# mcu1_secondary.net
KiCad netlist of a schematic drawn in Altium Designer
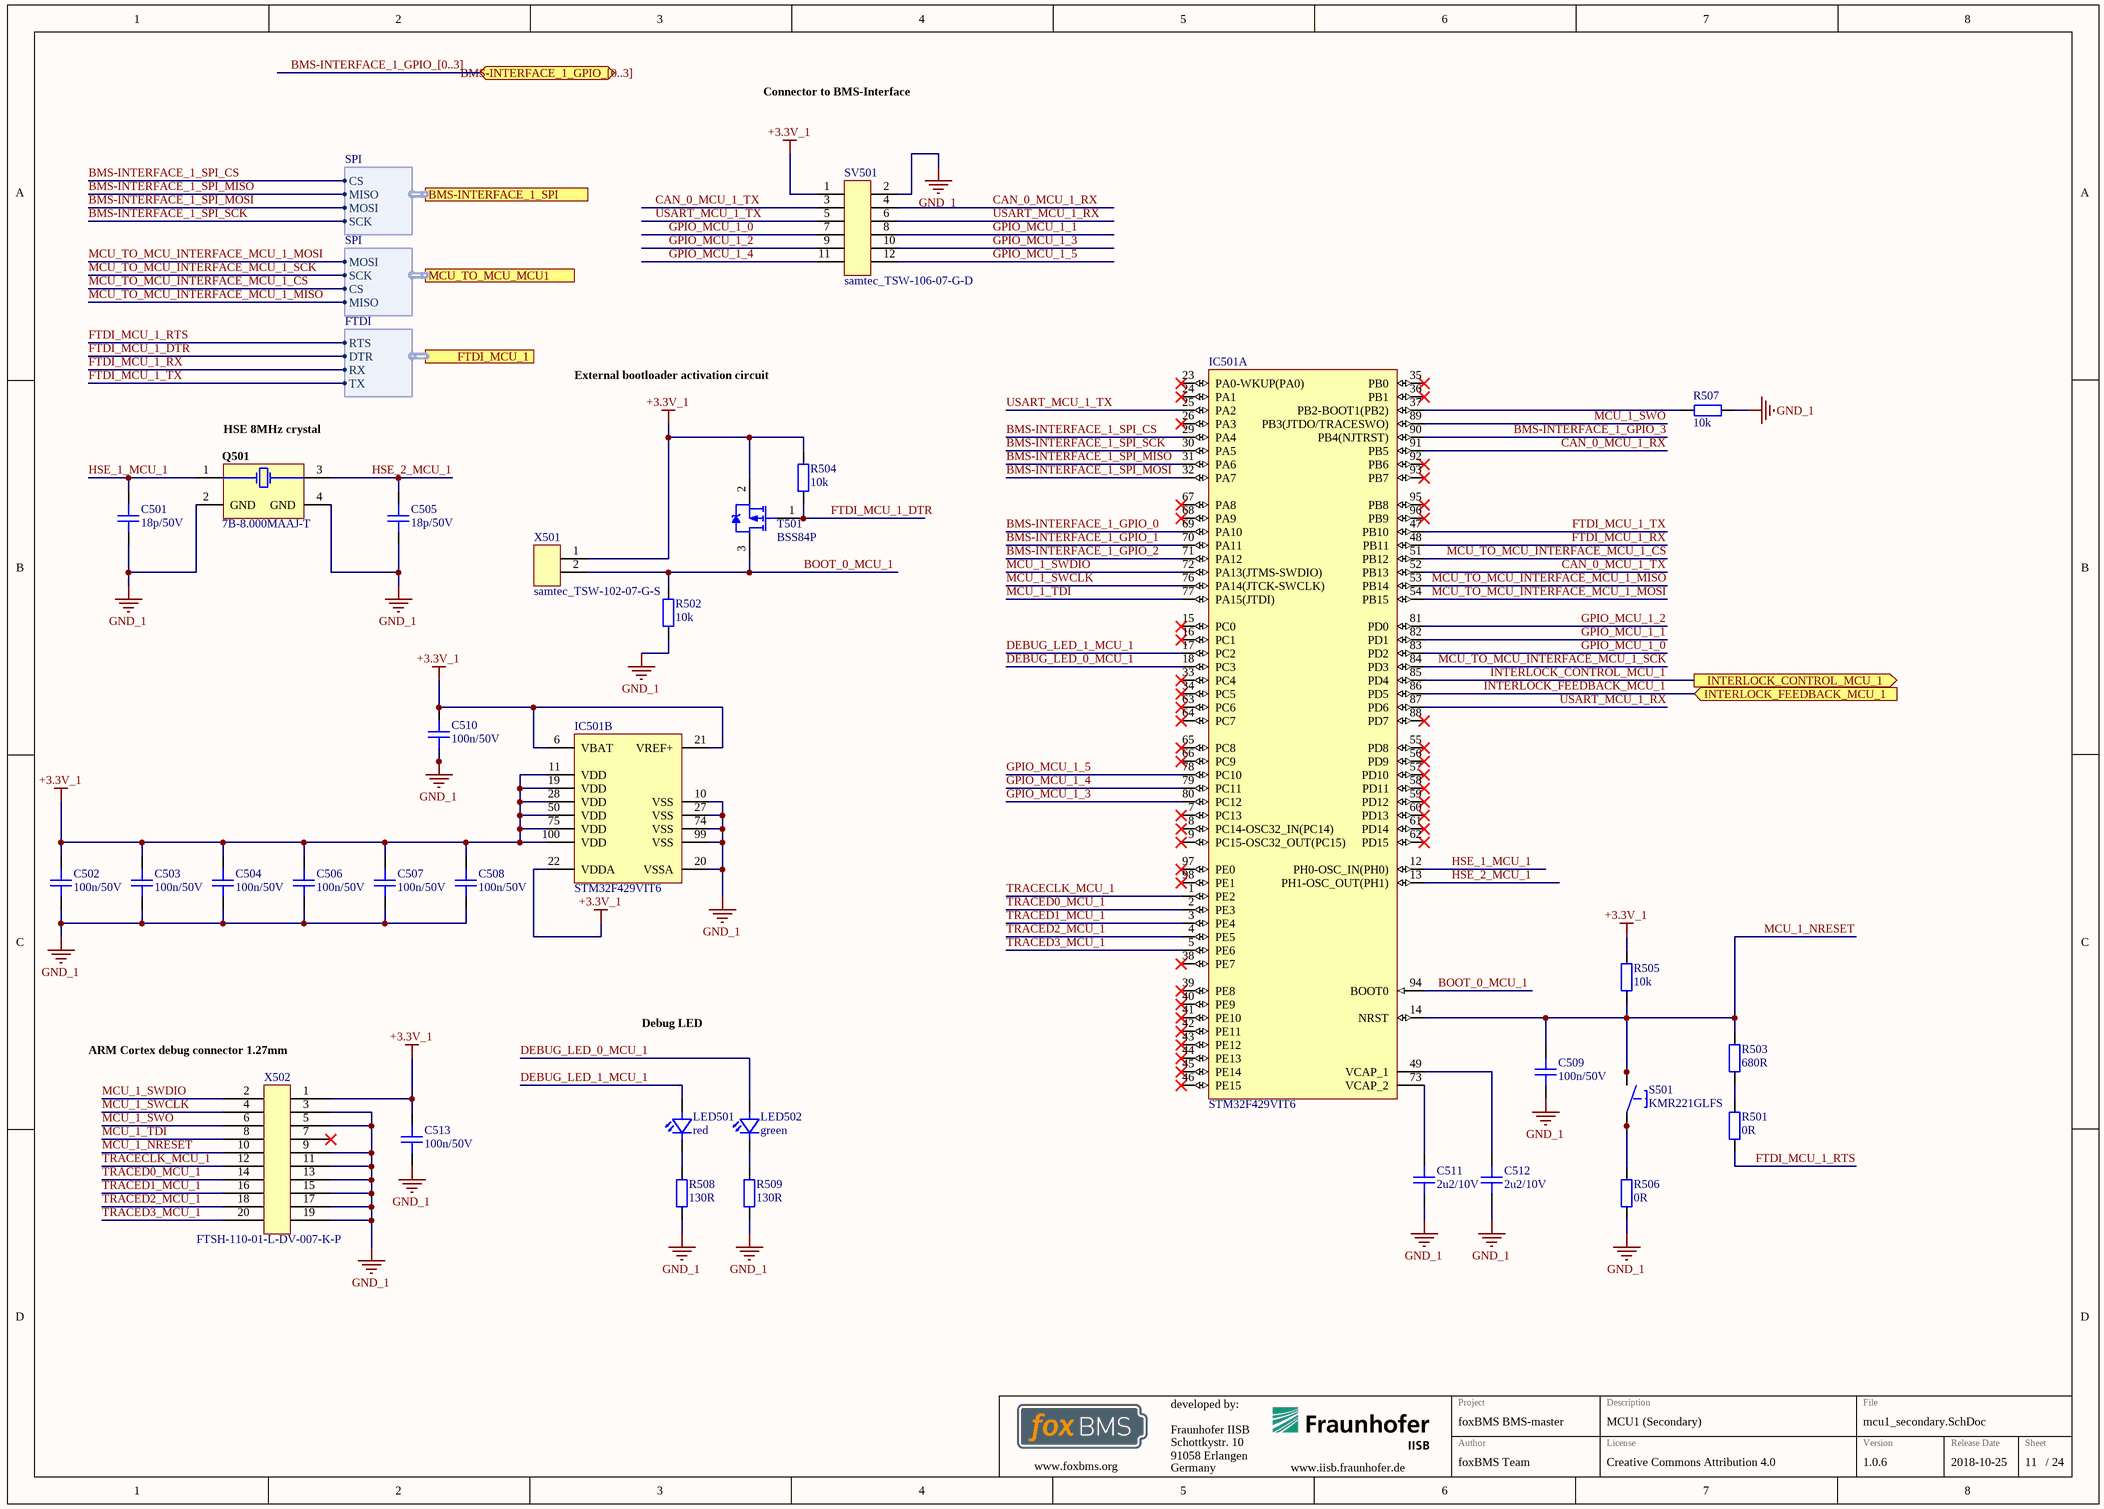
[diagram p0: mcu1_secondary.SchDoc]

(export (version "E")
  (design (tool "Eeschema 10.0.6"))
  (components
    (comp (ref "C501")
      (value "18p/50V")
      (footprint "CAPC1608X08N")
      (description "MLCC")
      (fields (field (name "PART NUMBER") "gen_C_ceramic_18p_50V_C0G_0603"))
      (libsource (lib "OE750") (part "C"))
    )
    (comp (ref "C502")
      (value "100n/50V")
      (footprint "CAPC1608X08N")
      (description "MLCC")
      (fields (field (name "PART NUMBER") "gen_C_ceramic_100n_50V_X7R_0603"))
      (libsource (lib "OE750") (part "C"))
    )
    (comp (ref "C503")
      (value "100n/50V")
      (footprint "CAPC1608X08N")
      (description "MLCC")
      (fields (field (name "PART NUMBER") "gen_C_ceramic_100n_50V_X7R_0603"))
      (libsource (lib "OE750") (part "C"))
    )
    (comp (ref "C504")
      (value "100n/50V")
      (footprint "CAPC1608X08N")
      (description "MLCC")
      (fields (field (name "PART NUMBER") "gen_C_ceramic_100n_50V_X7R_0603"))
      (libsource (lib "OE750") (part "C"))
    )
    (comp (ref "C505")
      (value "18p/50V")
      (footprint "CAPC1608X08N")
      (description "MLCC")
      (fields (field (name "PART NUMBER") "gen_C_ceramic_18p_50V_C0G_0603"))
      (libsource (lib "OE750") (part "C"))
    )
    (comp (ref "C506")
      (value "100n/50V")
      (footprint "CAPC1608X08N")
      (description "MLCC")
      (fields (field (name "PART NUMBER") "gen_C_ceramic_100n_50V_X7R_0603"))
      (libsource (lib "OE750") (part "C"))
    )
    (comp (ref "C507")
      (value "100n/50V")
      (footprint "CAPC1608X08N")
      (description "MLCC")
      (fields (field (name "PART NUMBER") "gen_C_ceramic_100n_50V_X7R_0603"))
      (libsource (lib "OE750") (part "C"))
    )
    (comp (ref "C508")
      (value "100n/50V")
      (footprint "CAPC1608X08N")
      (description "MLCC")
      (fields (field (name "PART NUMBER") "gen_C_ceramic_100n_50V_X7R_0603"))
      (libsource (lib "OE750") (part "C"))
    )
    (comp (ref "C509")
      (value "100n/50V")
      (footprint "CAPC1608X08N")
      (description "MLCC")
      (fields (field (name "PART NUMBER") "gen_C_ceramic_100n_50V_X7R_0603"))
      (libsource (lib "OE750") (part "C"))
    )
    (comp (ref "C510")
      (value "100n/50V")
      (footprint "CAPC1608X08N")
      (description "MLCC")
      (fields (field (name "PART NUMBER") "gen_C_ceramic_100n_50V_X7R_0603"))
      (libsource (lib "OE750") (part "C"))
    )
    (comp (ref "C511")
      (value "2u2/10V")
      (footprint "CAPC1608X08N")
      (description "MLCC")
      (fields (field (name "PART NUMBER") "gen_C_ceramic_2u2_10V_X5R_0603"))
      (libsource (lib "OE750") (part "C"))
    )
    (comp (ref "C512")
      (value "2u2/10V")
      (footprint "CAPC1608X08N")
      (description "MLCC")
      (fields (field (name "PART NUMBER") "gen_C_ceramic_2u2_10V_X5R_0603"))
      (libsource (lib "OE750") (part "C"))
    )
    (comp (ref "C513")
      (value "100n/50V")
      (footprint "CAPC1608X08N")
      (description "MLCC")
      (fields (field (name "PART NUMBER") "gen_C_ceramic_100n_50V_X7R_0603"))
      (libsource (lib "OE750") (part "C"))
    )
    (comp (ref "IC501")
      (value "STM32F429VIT6")
      (footprint "STM-LQFP100_N")
      (fields (field (name "MANUFACTURER") "STMicroelectronics"))
      (libsource (lib "Altium Content Vault") (part "MC-ARM-STM32F4X9-SQ100"))
    )
    (comp (ref "LED501")
      (value "red")
      (footprint "LEDC1608X07N")
      (description "LED")
      (fields (field (name "PART NUMBER") "gen_LED_0603_red"))
      (libsource (lib "OE750") (part "D_LED"))
    )
    (comp (ref "LED502")
      (value "green")
      (footprint "LEDC1608X07N")
      (description "LED")
      (fields (field (name "PART NUMBER") "gen_LED_0603_green"))
      (libsource (lib "OE750") (part "D_LED"))
    )
    (comp (ref "Q501")
      (value "7B-8.000MAAJ-T")
      (footprint "TXC-7B-4_V")
      (description "SMD Seam Sealing Crystal, 8 MHz, +/- 30 ppm, 18 pF, -10 to 70 degC, 4-Pin SMD, RoHS, Tape and Reel")
      (fields (field (name "TOLERANCE") "1%"))
      (libsource (lib "Altium Content Vault") (part "XTAL-1-3-4"))
    )
    (comp (ref "R501")
      (value "0R")
      (footprint "RESC1608X05N")
      (description "SMD Resistor 0R 0603")
      (fields (field (name "PART NUMBER") "gen_R_0R_0603") (field (name "POWER") "0.1W"))
      (libsource (lib "OE750") (part "R"))
    )
    (comp (ref "R502")
      (value "10k")
      (footprint "RESC1608X05N")
      (description "SMD Resistor 10k 0603")
      (fields (field (name "PART NUMBER") "gen_R_10k_0603") (field (name "TOLERANCE") "1%"))
      (libsource (lib "OE750") (part "R"))
    )
    (comp (ref "R503")
      (value "680R")
      (footprint "RESC1608X05N")
      (description "SMD Resistor 680R 0603")
      (fields (field (name "PART NUMBER") "gen_R_680R_0603") (field (name "TOLERANCE") "1%"))
      (libsource (lib "OE750") (part "R"))
    )
    (comp (ref "R504")
      (value "10k")
      (footprint "RESC1608X05N")
      (description "SMD Resistor 10k 0603")
      (fields (field (name "PART NUMBER") "gen_R_10k_0603") (field (name "TOLERANCE") "1%"))
      (libsource (lib "OE750") (part "R"))
    )
    (comp (ref "R505")
      (value "10k")
      (footprint "RESC1608X05N")
      (description "SMD Resistor 10k 0603")
      (fields (field (name "PART NUMBER") "gen_R_10k_0603") (field (name "TOLERANCE") "1%"))
      (libsource (lib "OE750") (part "R"))
    )
    (comp (ref "R506")
      (value "0R")
      (footprint "RESC1608X05N")
      (description "SMD Resistor 0R 0603")
      (fields (field (name "PART NUMBER") "gen_R_0R_0603") (field (name "POWER") "0.1W"))
      (libsource (lib "OE750") (part "R"))
    )
    (comp (ref "R507")
      (value "10k")
      (footprint "RESC1608X05N")
      (description "SMD Resistor 10k 0603")
      (fields (field (name "PART NUMBER") "gen_R_10k_0603") (field (name "TOLERANCE") "1%"))
      (libsource (lib "OE750") (part "R"))
    )
    (comp (ref "R508")
      (value "130R")
      (footprint "RESC1608X05N")
      (description "SMD Resistor 130R 0603")
      (fields (field (name "PART NUMBER") "gen_R_130R_0603") (field (name "TOLERANCE") "1%"))
      (libsource (lib "OE750") (part "R"))
    )
    (comp (ref "R509")
      (value "130R")
      (footprint "RESC1608X05N")
      (description "SMD Resistor 130R 0603")
      (fields (field (name "PART NUMBER") "gen_R_130R_0603") (field (name "TOLERANCE") "1%"))
      (libsource (lib "OE750") (part "R"))
    )
    (comp (ref "S501")
      (value "KMR221GLFS")
      (footprint "KMR2_Series")
      (description "Microminiature Tactile Switch")
      (fields (field (name "MANUFACTURER") "CK Components"))
      (libsource (lib "OE750") (part "Switch_4_Pin"))
    )
    (comp (ref "SV501")
      (value "samtec_TSW-106-07-G-D")
      (footprint "Pinheader_2.54_2x6")
      (description "Board-To-Board Connector, Vertical, 2.54 mm, 12 Contacts, Header, TSW Series, Through Hole, 2 Rows")
      (fields (field (name "MANUFACTURER") "Samtec"))
      (libsource (lib "OE750") (part "X2x6"))
    )
    (comp (ref "T501")
      (value "BSS84P")
      (footprint "INF-PG-SOT23_N")
      (fields (field (name "MANUFACTURER") "Infineon"))
      (libsource (lib "Altium Content Vault") (part "INF-PEMOS-GSD-3-B"))
    )
    (comp (ref "X501")
      (value "samtec_TSW-102-07-G-S")
      (footprint "Pinheader_2.54_2")
      (description "Board-To-Board Connector, Vertical, 2.54 mm, 2 Contacts, Header, TSW Series, Through Hole, 1 Row")
      (fields (field (name "MANUFACTURER") "Samtec"))
      (libsource (lib "OE750") (part "X2"))
    )
    (comp (ref "X502")
      (value "FTSH-110-01-L-DV-007-K-P")
      (footprint "CORTEX_DEBUG_20_PIN")
      (description "Board-To-Board Connector, ARM Cortex Debug Header 20 Pin")
      (fields
        (field (name "PART NUMBER") "samtec_FTSH-110-01-L-DV-007-K-P")
        (field (name "MANUFACTURER") "Samtec")
      )
      (libsource (lib "OE750") (part "CORTEX_DEBUG_20_PIN"))
    )
  )
  (nets
    (net (code "3") (name "+3.3V_1") (class "Default")
      (node (ref "C502") (pin "1") (pinfunction "1_1") (pintype "passive"))
      (node (ref "C503") (pin "1") (pinfunction "1_1") (pintype "passive"))
      (node (ref "C504") (pin "1") (pinfunction "1_1") (pintype "passive"))
      (node (ref "C506") (pin "1") (pinfunction "1_1") (pintype "passive"))
      (node (ref "C507") (pin "1") (pinfunction "1_1") (pintype "passive"))
      (node (ref "C508") (pin "1") (pinfunction "1_1") (pintype "passive"))
      (node (ref "C510") (pin "1") (pinfunction "1_1") (pintype "passive"))
      (node (ref "C513") (pin "1") (pinfunction "1_1") (pintype "passive"))
      (node (ref "IC501") (pin "100") (pinfunction "VDD_100") (pintype "power_in"))
      (node (ref "IC501") (pin "11") (pinfunction "VDD_11") (pintype "power_in"))
      (node (ref "IC501") (pin "19") (pinfunction "VDD_19") (pintype "power_in"))
      (node (ref "IC501") (pin "21") (pinfunction "VREF+_21") (pintype "power_in"))
      (node (ref "IC501") (pin "22") (pinfunction "VDDA_22") (pintype "power_in"))
      (node (ref "IC501") (pin "28") (pinfunction "VDD_28") (pintype "power_in"))
      (node (ref "IC501") (pin "50") (pinfunction "VDD_50") (pintype "power_in"))
      (node (ref "IC501") (pin "6") (pinfunction "VBAT_6") (pintype "power_in"))
      (node (ref "IC501") (pin "75") (pinfunction "VDD_75") (pintype "power_in"))
      (node (ref "R504") (pin "2") (pinfunction "2_2") (pintype "passive"))
      (node (ref "R505") (pin "2") (pinfunction "2_2") (pintype "passive"))
      (node (ref "SV501") (pin "1") (pintype "passive"))
      (node (ref "T501") (pin "2") (pinfunction "SOURCE_2") (pintype "passive"))
      (node (ref "X501") (pin "1") (pintype "passive"))
      (node (ref "X502") (pin "1") (pintype "passive"))
    )
    (net (code "4") (name "/BMS-INTERFACE_1_GPIO_0") (class "Default")
      (node (ref "IC501") (pin "69") (pinfunction "PA10_69") (pintype "bidirectional"))
    )
    (net (code "5") (name "/BMS-INTERFACE_1_GPIO_1") (class "Default")
      (node (ref "IC501") (pin "70") (pinfunction "PA11_70") (pintype "bidirectional"))
    )
    (net (code "6") (name "/BMS-INTERFACE_1_GPIO_2") (class "Default")
      (node (ref "IC501") (pin "71") (pinfunction "PA12_71") (pintype "bidirectional"))
    )
    (net (code "7") (name "/BMS-INTERFACE_1_GPIO_3") (class "Default")
      (node (ref "IC501") (pin "90") (pinfunction "PB4(NJTRST)_90") (pintype "bidirectional"))
    )
    (net (code "9") (name "/BMS-INTERFACE_1_SPI_CS") (class "Default")
      (node (ref "IC501") (pin "29") (pinfunction "PA4_29") (pintype "bidirectional"))
    )
    (net (code "10") (name "/BMS-INTERFACE_1_SPI_MISO") (class "Default")
      (node (ref "IC501") (pin "31") (pinfunction "PA6_31") (pintype "bidirectional"))
    )
    (net (code "11") (name "/BMS-INTERFACE_1_SPI_MOSI") (class "Default")
      (node (ref "IC501") (pin "32") (pinfunction "PA7_32") (pintype "bidirectional"))
    )
    (net (code "12") (name "/BMS-INTERFACE_1_SPI_SCK") (class "Default")
      (node (ref "IC501") (pin "30") (pinfunction "PA5_30") (pintype "bidirectional"))
    )
    (net (code "13") (name "/BOOT_0_MCU_1") (class "Default")
      (node (ref "IC501") (pin "94") (pinfunction "BOOT0_94") (pintype "input"))
      (node (ref "R502") (pin "2") (pinfunction "2_2") (pintype "passive"))
      (node (ref "T501") (pin "3") (pinfunction "DRAIN_3") (pintype "passive"))
      (node (ref "X501") (pin "2") (pintype "passive"))
    )
    (net (code "14") (name "/CAN_0_MCU_1_RX") (class "Default")
      (node (ref "IC501") (pin "91") (pinfunction "PB5_91") (pintype "bidirectional"))
      (node (ref "SV501") (pin "4") (pintype "passive"))
    )
    (net (code "15") (name "/CAN_0_MCU_1_TX") (class "Default")
      (node (ref "IC501") (pin "52") (pinfunction "PB13_52") (pintype "bidirectional"))
      (node (ref "SV501") (pin "3") (pintype "passive"))
    )
    (net (code "16") (name "/DEBUG_LED_0_MCU_1") (class "Default")
      (node (ref "IC501") (pin "18") (pinfunction "PC3_18") (pintype "bidirectional"))
      (node (ref "LED502") (pin "2") (pinfunction "A_2") (pintype "passive"))
    )
    (net (code "17") (name "/DEBUG_LED_1_MCU_1") (class "Default")
      (node (ref "IC501") (pin "17") (pinfunction "PC2_17") (pintype "bidirectional"))
      (node (ref "LED501") (pin "2") (pinfunction "A_2") (pintype "passive"))
    )
    (net (code "18") (name "/FTDI_MCU_1_DTR") (class "Default")
      (node (ref "R504") (pin "1") (pinfunction "1_1") (pintype "passive"))
      (node (ref "T501") (pin "1") (pinfunction "GATE_1") (pintype "passive"))
    )
    (net (code "19") (name "/FTDI_MCU_1_RTS") (class "Default")
      (node (ref "R501") (pin "2") (pinfunction "2_2") (pintype "passive"))
    )
    (net (code "20") (name "/FTDI_MCU_1_RX") (class "Default")
      (node (ref "IC501") (pin "48") (pinfunction "PB11_48") (pintype "bidirectional"))
    )
    (net (code "21") (name "/FTDI_MCU_1_TX") (class "Default")
      (node (ref "IC501") (pin "47") (pinfunction "PB10_47") (pintype "bidirectional"))
    )
    (net (code "22") (name "/GPIO_MCU_1_0") (class "Default")
      (node (ref "IC501") (pin "83") (pinfunction "PD2_83") (pintype "bidirectional"))
      (node (ref "SV501") (pin "7") (pintype "passive"))
    )
    (net (code "23") (name "/GPIO_MCU_1_1") (class "Default")
      (node (ref "IC501") (pin "82") (pinfunction "PD1_82") (pintype "bidirectional"))
      (node (ref "SV501") (pin "8") (pintype "passive"))
    )
    (net (code "24") (name "/GPIO_MCU_1_2") (class "Default")
      (node (ref "IC501") (pin "81") (pinfunction "PD0_81") (pintype "bidirectional"))
      (node (ref "SV501") (pin "9") (pintype "passive"))
    )
    (net (code "25") (name "/GPIO_MCU_1_3") (class "Default")
      (node (ref "IC501") (pin "80") (pinfunction "PC12_80") (pintype "bidirectional"))
      (node (ref "SV501") (pin "10") (pintype "passive"))
    )
    (net (code "26") (name "/GPIO_MCU_1_4") (class "Default")
      (node (ref "IC501") (pin "79") (pinfunction "PC11_79") (pintype "bidirectional"))
      (node (ref "SV501") (pin "11") (pintype "passive"))
    )
    (net (code "27") (name "/GPIO_MCU_1_5") (class "Default")
      (node (ref "IC501") (pin "78") (pinfunction "PC10_78") (pintype "bidirectional"))
      (node (ref "SV501") (pin "12") (pintype "passive"))
    )
    (net (code "28") (name "/HSE_1_MCU_1") (class "Default")
      (node (ref "C501") (pin "2") (pinfunction "2_2") (pintype "passive"))
      (node (ref "IC501") (pin "12") (pinfunction "PH0-OSC_IN(PH0)_12") (pintype "bidirectional"))
      (node (ref "Q501") (pin "1") (pinfunction "X1_1") (pintype "passive"))
    )
    (net (code "29") (name "/HSE_2_MCU_1") (class "Default")
      (node (ref "C505") (pin "1") (pinfunction "1_1") (pintype "passive"))
      (node (ref "IC501") (pin "13") (pinfunction "PH1-OSC_OUT(PH1)_13") (pintype "bidirectional"))
      (node (ref "Q501") (pin "3") (pinfunction "X2_3") (pintype "passive"))
    )
    (net (code "30") (name "/INTERLOCK_CONTROL_MCU_1") (class "Default")
      (node (ref "IC501") (pin "85") (pinfunction "PD4_85") (pintype "bidirectional"))
    )
    (net (code "31") (name "/INTERLOCK_FEEDBACK_MCU_1") (class "Default")
      (node (ref "IC501") (pin "86") (pinfunction "PD5_86") (pintype "bidirectional"))
    )
    (net (code "32") (name "/MCU_1_NRESET") (class "Default")
      (node (ref "C509") (pin "1") (pinfunction "1_1") (pintype "passive"))
      (node (ref "IC501") (pin "14") (pinfunction "NRST_14") (pintype "bidirectional"))
      (node (ref "R503") (pin "1") (pinfunction "1_1") (pintype "passive"))
      (node (ref "R505") (pin "1") (pinfunction "1_1") (pintype "passive"))
      (node (ref "S501") (pin "3") (pintype "passive"))
      (node (ref "S501") (pin "4") (pintype "passive"))
      (node (ref "X502") (pin "10") (pintype "passive"))
    )
    (net (code "33") (name "/MCU_1_SWCLK") (class "Default")
      (node (ref "IC501") (pin "76") (pinfunction "PA14(JTCK-SWCLK)_76") (pintype "bidirectional"))
      (node (ref "X502") (pin "4") (pintype "passive"))
    )
    (net (code "34") (name "/MCU_1_SWDIO") (class "Default")
      (node (ref "IC501") (pin "72") (pinfunction "PA13(JTMS-SWDIO)_72") (pintype "bidirectional"))
      (node (ref "X502") (pin "2") (pintype "passive"))
    )
    (net (code "35") (name "/MCU_1_SWO") (class "Default")
      (node (ref "IC501") (pin "89") (pinfunction "PB3(JTDO/TRACESWO)_89") (pintype "bidirectional"))
      (node (ref "X502") (pin "6") (pintype "passive"))
    )
    (net (code "36") (name "/MCU_1_TDI") (class "Default")
      (node (ref "IC501") (pin "77") (pinfunction "PA15(JTDI)_77") (pintype "bidirectional"))
      (node (ref "X502") (pin "8") (pintype "passive"))
    )
    (net (code "37") (name "/MCU_TO_MCU_INTERFACE_MCU_1_CS") (class "Default")
      (node (ref "IC501") (pin "51") (pinfunction "PB12_51") (pintype "bidirectional"))
    )
    (net (code "38") (name "/MCU_TO_MCU_INTERFACE_MCU_1_MISO") (class "Default")
      (node (ref "IC501") (pin "53") (pinfunction "PB14_53") (pintype "bidirectional"))
    )
    (net (code "39") (name "/MCU_TO_MCU_INTERFACE_MCU_1_MOSI") (class "Default")
      (node (ref "IC501") (pin "54") (pinfunction "PB15_54") (pintype "bidirectional"))
    )
    (net (code "40") (name "/MCU_TO_MCU_INTERFACE_MCU_1_SCK") (class "Default")
      (node (ref "IC501") (pin "84") (pinfunction "PD3_84") (pintype "bidirectional"))
    )
    (net (code "41") (name "/TRACECLK_MCU_1") (class "Default")
      (node (ref "IC501") (pin "1") (pinfunction "PE2_1") (pintype "bidirectional"))
      (node (ref "X502") (pin "12") (pintype "passive"))
    )
    (net (code "42") (name "/TRACED0_MCU_1") (class "Default")
      (node (ref "IC501") (pin "2") (pinfunction "PE3_2") (pintype "bidirectional"))
      (node (ref "X502") (pin "14") (pintype "passive"))
    )
    (net (code "43") (name "/TRACED1_MCU_1") (class "Default")
      (node (ref "IC501") (pin "3") (pinfunction "PE4_3") (pintype "bidirectional"))
      (node (ref "X502") (pin "16") (pintype "passive"))
    )
    (net (code "44") (name "/TRACED2_MCU_1") (class "Default")
      (node (ref "IC501") (pin "4") (pinfunction "PE5_4") (pintype "bidirectional"))
      (node (ref "X502") (pin "18") (pintype "passive"))
    )
    (net (code "45") (name "/TRACED3_MCU_1") (class "Default")
      (node (ref "IC501") (pin "5") (pinfunction "PE6_5") (pintype "bidirectional"))
      (node (ref "X502") (pin "20") (pintype "passive"))
    )
    (net (code "46") (name "/USART_MCU_1_RX") (class "Default")
      (node (ref "IC501") (pin "87") (pinfunction "PD6_87") (pintype "bidirectional"))
      (node (ref "SV501") (pin "6") (pintype "passive"))
    )
    (net (code "47") (name "/USART_MCU_1_TX") (class "Default")
      (node (ref "IC501") (pin "25") (pinfunction "PA2_25") (pintype "bidirectional"))
      (node (ref "SV501") (pin "5") (pintype "passive"))
    )
    (net (code "50") (name "GND_1") (class "Default")
      (node (ref "C501") (pin "1") (pinfunction "1_1") (pintype "passive"))
      (node (ref "C502") (pin "2") (pinfunction "2_2") (pintype "passive"))
      (node (ref "C503") (pin "2") (pinfunction "2_2") (pintype "passive"))
      (node (ref "C504") (pin "2") (pinfunction "2_2") (pintype "passive"))
      (node (ref "C505") (pin "2") (pinfunction "2_2") (pintype "passive"))
      (node (ref "C506") (pin "2") (pinfunction "2_2") (pintype "passive"))
      (node (ref "C507") (pin "2") (pinfunction "2_2") (pintype "passive"))
      (node (ref "C508") (pin "2") (pinfunction "2_2") (pintype "passive"))
      (node (ref "C509") (pin "2") (pinfunction "2_2") (pintype "passive"))
      (node (ref "C510") (pin "2") (pinfunction "2_2") (pintype "passive"))
      (node (ref "C511") (pin "2") (pinfunction "2_2") (pintype "passive"))
      (node (ref "C512") (pin "2") (pinfunction "2_2") (pintype "passive"))
      (node (ref "C513") (pin "2") (pinfunction "2_2") (pintype "passive"))
      (node (ref "IC501") (pin "10") (pinfunction "VSS_10") (pintype "power_in"))
      (node (ref "IC501") (pin "20") (pinfunction "VSSA_20") (pintype "power_in"))
      (node (ref "IC501") (pin "27") (pinfunction "VSS_27") (pintype "power_in"))
      (node (ref "IC501") (pin "74") (pinfunction "VSS_74") (pintype "power_in"))
      (node (ref "IC501") (pin "99") (pinfunction "VSS_99") (pintype "power_in"))
      (node (ref "Q501") (pin "2") (pinfunction "GND_2") (pintype "power_in"))
      (node (ref "Q501") (pin "4") (pinfunction "GND_4") (pintype "power_in"))
      (node (ref "R502") (pin "1") (pinfunction "1_1") (pintype "passive"))
      (node (ref "R506") (pin "1") (pinfunction "1_1") (pintype "passive"))
      (node (ref "R507") (pin "1") (pinfunction "1_1") (pintype "passive"))
      (node (ref "R508") (pin "1") (pinfunction "1_1") (pintype "passive"))
      (node (ref "R509") (pin "1") (pinfunction "1_1") (pintype "passive"))
      (node (ref "SV501") (pin "2") (pintype "passive"))
      (node (ref "X502") (pin "11") (pintype "passive"))
      (node (ref "X502") (pin "13") (pintype "passive"))
      (node (ref "X502") (pin "15") (pintype "passive"))
      (node (ref "X502") (pin "17") (pintype "passive"))
      (node (ref "X502") (pin "19") (pintype "passive"))
      (node (ref "X502") (pin "3") (pintype "passive"))
      (node (ref "X502") (pin "5") (pintype "passive"))
      (node (ref "X502") (pin "9") (pintype "passive"))
    )
    (net (code "51") (name "Net-(IC501A-PB2-BOOT1(PB2))") (class "Default")
      (node (ref "IC501") (pin "37") (pinfunction "PB2-BOOT1(PB2)_37") (pintype "bidirectional"))
      (node (ref "R507") (pin "2") (pinfunction "2_2") (pintype "passive"))
    )
    (net (code "52") (name "Net-(IC501A-VCAP_1)") (class "Default")
      (node (ref "C512") (pin "1") (pinfunction "1_1") (pintype "passive"))
      (node (ref "IC501") (pin "49") (pinfunction "VCAP_1_49") (pintype "power_in"))
    )
    (net (code "53") (name "Net-(IC501A-VCAP_2)") (class "Default")
      (node (ref "C511") (pin "1") (pinfunction "1_1") (pintype "passive"))
      (node (ref "IC501") (pin "73") (pinfunction "VCAP_2_73") (pintype "power_in"))
    )
    (net (code "54") (name "Net-(LED501-C)") (class "Default")
      (node (ref "LED501") (pin "1") (pinfunction "C_1") (pintype "passive"))
      (node (ref "R508") (pin "2") (pinfunction "2_2") (pintype "passive"))
    )
    (net (code "55") (name "Net-(LED502-C)") (class "Default")
      (node (ref "LED502") (pin "1") (pinfunction "C_1") (pintype "passive"))
      (node (ref "R509") (pin "2") (pinfunction "2_2") (pintype "passive"))
    )
    (net (code "56") (name "Net-(R501-Pad1)") (class "Default")
      (node (ref "R501") (pin "1") (pinfunction "1_1") (pintype "passive"))
      (node (ref "R503") (pin "2") (pinfunction "2_2") (pintype "passive"))
    )
    (net (code "57") (name "Net-(R506-Pad2)") (class "Default")
      (node (ref "R506") (pin "2") (pinfunction "2_2") (pintype "passive"))
      (node (ref "S501") (pin "1") (pintype "passive"))
      (node (ref "S501") (pin "2") (pintype "passive"))
    )
    (net (code "58") (name "unconnected-(IC501A-PA0-WKUP(PA0)-Pad23)") (class "Default")
      (node (ref "IC501") (pin "23") (pinfunction "PA0-WKUP(PA0)_23") (pintype "bidirectional+no_connect"))
    )
    (net (code "59") (name "unconnected-(IC501A-PA1-Pad24)") (class "Default")
      (node (ref "IC501") (pin "24") (pinfunction "PA1_24") (pintype "bidirectional+no_connect"))
    )
    (net (code "60") (name "unconnected-(IC501A-PA3-Pad26)") (class "Default")
      (node (ref "IC501") (pin "26") (pinfunction "PA3_26") (pintype "bidirectional+no_connect"))
    )
    (net (code "61") (name "unconnected-(IC501A-PA8-Pad67)") (class "Default")
      (node (ref "IC501") (pin "67") (pinfunction "PA8_67") (pintype "bidirectional+no_connect"))
    )
    (net (code "62") (name "unconnected-(IC501A-PA9-Pad68)") (class "Default")
      (node (ref "IC501") (pin "68") (pinfunction "PA9_68") (pintype "bidirectional+no_connect"))
    )
    (net (code "63") (name "unconnected-(IC501A-PB0-Pad35)") (class "Default")
      (node (ref "IC501") (pin "35") (pinfunction "PB0_35") (pintype "bidirectional+no_connect"))
    )
    (net (code "64") (name "unconnected-(IC501A-PB1-Pad36)") (class "Default")
      (node (ref "IC501") (pin "36") (pinfunction "PB1_36") (pintype "bidirectional+no_connect"))
    )
    (net (code "65") (name "unconnected-(IC501A-PB6-Pad92)") (class "Default")
      (node (ref "IC501") (pin "92") (pinfunction "PB6_92") (pintype "bidirectional+no_connect"))
    )
    (net (code "66") (name "unconnected-(IC501A-PB7-Pad93)") (class "Default")
      (node (ref "IC501") (pin "93") (pinfunction "PB7_93") (pintype "bidirectional+no_connect"))
    )
    (net (code "67") (name "unconnected-(IC501A-PB8-Pad95)") (class "Default")
      (node (ref "IC501") (pin "95") (pinfunction "PB8_95") (pintype "bidirectional+no_connect"))
    )
    (net (code "68") (name "unconnected-(IC501A-PB9-Pad96)") (class "Default")
      (node (ref "IC501") (pin "96") (pinfunction "PB9_96") (pintype "bidirectional+no_connect"))
    )
    (net (code "69") (name "unconnected-(IC501A-PC0-Pad15)") (class "Default")
      (node (ref "IC501") (pin "15") (pinfunction "PC0_15") (pintype "bidirectional+no_connect"))
    )
    (net (code "70") (name "unconnected-(IC501A-PC1-Pad16)") (class "Default")
      (node (ref "IC501") (pin "16") (pinfunction "PC1_16") (pintype "bidirectional+no_connect"))
    )
    (net (code "71") (name "unconnected-(IC501A-PC4-Pad33)") (class "Default")
      (node (ref "IC501") (pin "33") (pinfunction "PC4_33") (pintype "bidirectional+no_connect"))
    )
    (net (code "72") (name "unconnected-(IC501A-PC5-Pad34)") (class "Default")
      (node (ref "IC501") (pin "34") (pinfunction "PC5_34") (pintype "bidirectional+no_connect"))
    )
    (net (code "73") (name "unconnected-(IC501A-PC6-Pad63)") (class "Default")
      (node (ref "IC501") (pin "63") (pinfunction "PC6_63") (pintype "bidirectional+no_connect"))
    )
    (net (code "74") (name "unconnected-(IC501A-PC7-Pad64)") (class "Default")
      (node (ref "IC501") (pin "64") (pinfunction "PC7_64") (pintype "bidirectional+no_connect"))
    )
    (net (code "75") (name "unconnected-(IC501A-PC8-Pad65)") (class "Default")
      (node (ref "IC501") (pin "65") (pinfunction "PC8_65") (pintype "bidirectional+no_connect"))
    )
    (net (code "76") (name "unconnected-(IC501A-PC9-Pad66)") (class "Default")
      (node (ref "IC501") (pin "66") (pinfunction "PC9_66") (pintype "bidirectional+no_connect"))
    )
    (net (code "77") (name "unconnected-(IC501A-PC13-Pad7)") (class "Default")
      (node (ref "IC501") (pin "7") (pinfunction "PC13_7") (pintype "bidirectional+no_connect"))
    )
    (net (code "78") (name "unconnected-(IC501A-PC14-OSC32_IN(PC14)-Pad8)") (class "Default")
      (node (ref "IC501") (pin "8") (pinfunction "PC14-OSC32_IN(PC14)_8") (pintype "bidirectional+no_connect"))
    )
    (net (code "79") (name "unconnected-(IC501A-PC15-OSC32_OUT(PC15)-Pad9)") (class "Default")
      (node (ref "IC501") (pin "9") (pinfunction "PC15-OSC32_OUT(PC15)_9") (pintype "bidirectional+no_connect"))
    )
    (net (code "80") (name "unconnected-(IC501A-PD7-Pad88)") (class "Default")
      (node (ref "IC501") (pin "88") (pinfunction "PD7_88") (pintype "bidirectional+no_connect"))
    )
    (net (code "81") (name "unconnected-(IC501A-PD8-Pad55)") (class "Default")
      (node (ref "IC501") (pin "55") (pinfunction "PD8_55") (pintype "bidirectional+no_connect"))
    )
    (net (code "82") (name "unconnected-(IC501A-PD9-Pad56)") (class "Default")
      (node (ref "IC501") (pin "56") (pinfunction "PD9_56") (pintype "bidirectional+no_connect"))
    )
    (net (code "83") (name "unconnected-(IC501A-PD10-Pad57)") (class "Default")
      (node (ref "IC501") (pin "57") (pinfunction "PD10_57") (pintype "bidirectional+no_connect"))
    )
    (net (code "84") (name "unconnected-(IC501A-PD11-Pad58)") (class "Default")
      (node (ref "IC501") (pin "58") (pinfunction "PD11_58") (pintype "bidirectional+no_connect"))
    )
    (net (code "85") (name "unconnected-(IC501A-PD12-Pad59)") (class "Default")
      (node (ref "IC501") (pin "59") (pinfunction "PD12_59") (pintype "bidirectional+no_connect"))
    )
    (net (code "86") (name "unconnected-(IC501A-PD13-Pad60)") (class "Default")
      (node (ref "IC501") (pin "60") (pinfunction "PD13_60") (pintype "bidirectional+no_connect"))
    )
    (net (code "87") (name "unconnected-(IC501A-PD14-Pad61)") (class "Default")
      (node (ref "IC501") (pin "61") (pinfunction "PD14_61") (pintype "bidirectional+no_connect"))
    )
    (net (code "88") (name "unconnected-(IC501A-PD15-Pad62)") (class "Default")
      (node (ref "IC501") (pin "62") (pinfunction "PD15_62") (pintype "bidirectional+no_connect"))
    )
    (net (code "89") (name "unconnected-(IC501A-PE0-Pad97)") (class "Default")
      (node (ref "IC501") (pin "97") (pinfunction "PE0_97") (pintype "bidirectional+no_connect"))
    )
    (net (code "90") (name "unconnected-(IC501A-PE1-Pad98)") (class "Default")
      (node (ref "IC501") (pin "98") (pinfunction "PE1_98") (pintype "bidirectional+no_connect"))
    )
    (net (code "91") (name "unconnected-(IC501A-PE7-Pad38)") (class "Default")
      (node (ref "IC501") (pin "38") (pinfunction "PE7_38") (pintype "bidirectional+no_connect"))
    )
    (net (code "92") (name "unconnected-(IC501A-PE8-Pad39)") (class "Default")
      (node (ref "IC501") (pin "39") (pinfunction "PE8_39") (pintype "bidirectional+no_connect"))
    )
    (net (code "93") (name "unconnected-(IC501A-PE9-Pad40)") (class "Default")
      (node (ref "IC501") (pin "40") (pinfunction "PE9_40") (pintype "bidirectional+no_connect"))
    )
    (net (code "94") (name "unconnected-(IC501A-PE10-Pad41)") (class "Default")
      (node (ref "IC501") (pin "41") (pinfunction "PE10_41") (pintype "bidirectional+no_connect"))
    )
    (net (code "95") (name "unconnected-(IC501A-PE11-Pad42)") (class "Default")
      (node (ref "IC501") (pin "42") (pinfunction "PE11_42") (pintype "bidirectional+no_connect"))
    )
    (net (code "96") (name "unconnected-(IC501A-PE12-Pad43)") (class "Default")
      (node (ref "IC501") (pin "43") (pinfunction "PE12_43") (pintype "bidirectional+no_connect"))
    )
    (net (code "97") (name "unconnected-(IC501A-PE13-Pad44)") (class "Default")
      (node (ref "IC501") (pin "44") (pinfunction "PE13_44") (pintype "bidirectional+no_connect"))
    )
    (net (code "98") (name "unconnected-(IC501A-PE14-Pad45)") (class "Default")
      (node (ref "IC501") (pin "45") (pinfunction "PE14_45") (pintype "bidirectional+no_connect"))
    )
    (net (code "99") (name "unconnected-(IC501A-PE15-Pad46)") (class "Default")
      (node (ref "IC501") (pin "46") (pinfunction "PE15_46") (pintype "bidirectional+no_connect"))
    )
    (net (code "100") (name "unconnected-(X502-Pad7)") (class "Default")
      (node (ref "X502") (pin "7") (pintype "passive+no_connect"))
    )
  )
)
